# Power_5v.net
KiCad netlist of a schematic drawn in Altium Designer
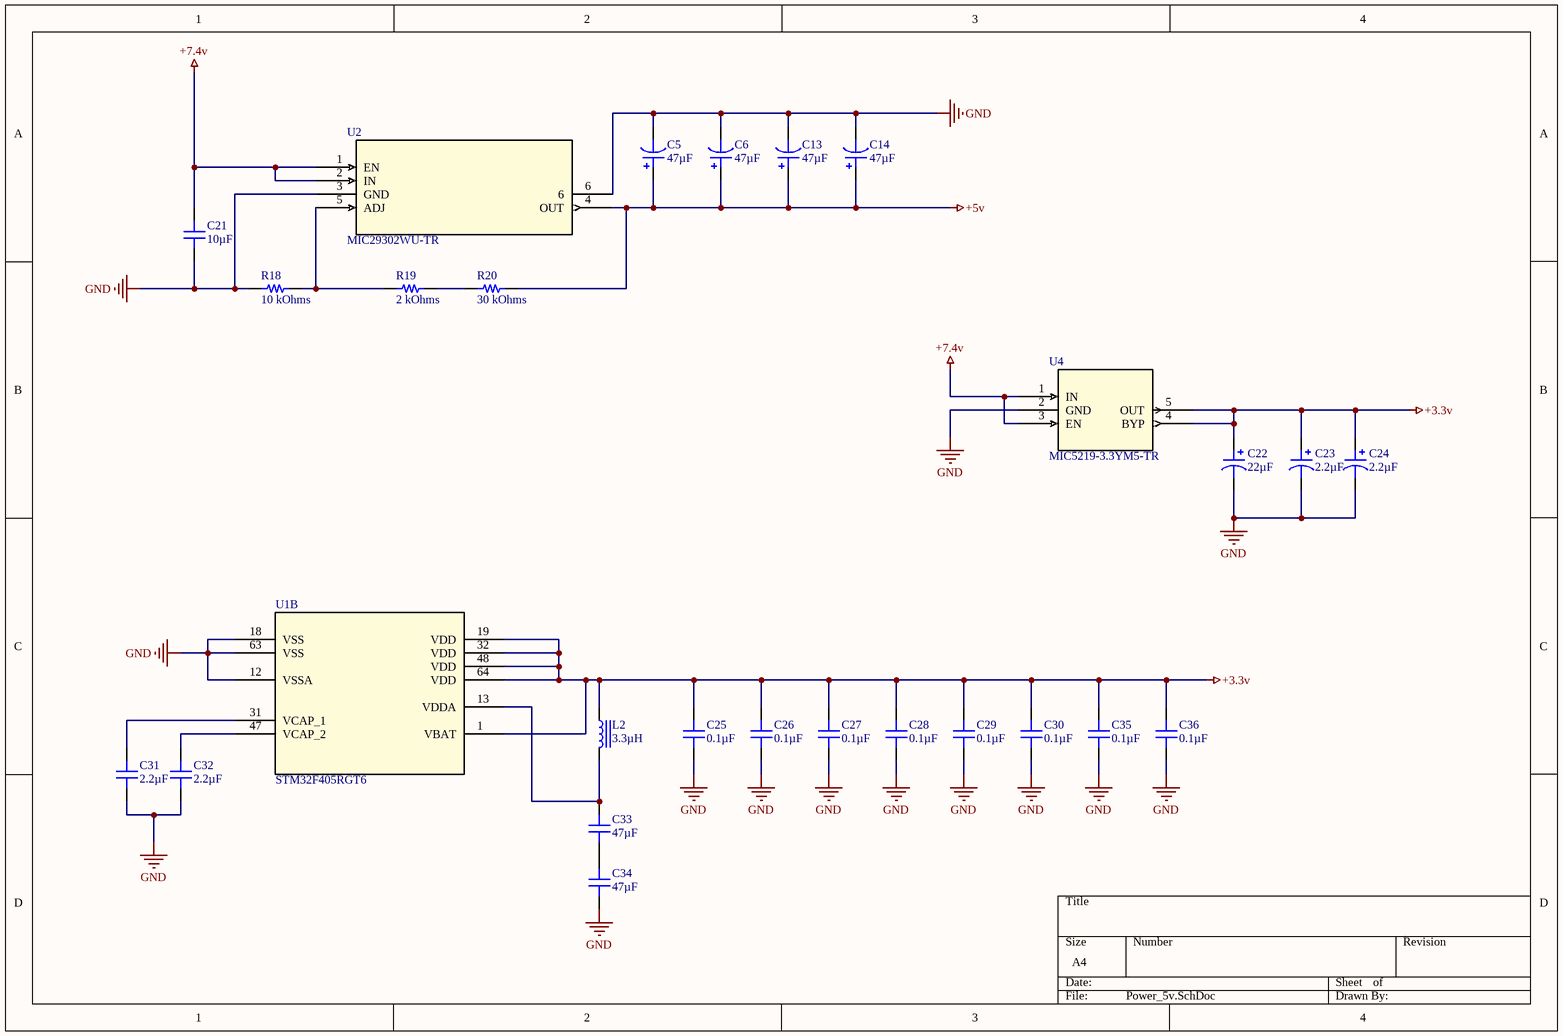
[diagram p0: Power_5v.SchDoc]

(export (version "E")
  (design (tool "Eeschema 10.0.6"))
  (components
    (comp (ref "C5")
      (value "47µF")
      (footprint "CAP POL 1411_3528")
      (description "CAP TANT 47UF 10% 10V 1411")
      (fields (field (name "PART NUMBER") "TPSB476K010R0250") (field (name "MANUFACTURER") "AVX Corporation"))
      (libsource (lib "Celestial Altium Library - altium_library") (part "Polarised Capacitor"))
    )
    (comp (ref "C6")
      (value "47µF")
      (footprint "CAP POL 1411_3528")
      (description "CAP TANT 47UF 10% 10V 1411")
      (fields (field (name "PART NUMBER") "TPSB476K010R0250") (field (name "MANUFACTURER") "AVX Corporation"))
      (libsource (lib "Celestial Altium Library - altium_library") (part "Polarised Capacitor"))
    )
    (comp (ref "C13")
      (value "47µF")
      (footprint "CAP POL 1411_3528")
      (description "CAP TANT 47UF 10% 10V 1411")
      (fields (field (name "PART NUMBER") "TPSB476K010R0250") (field (name "MANUFACTURER") "AVX Corporation"))
      (libsource (lib "Celestial Altium Library - altium_library") (part "Polarised Capacitor"))
    )
    (comp (ref "C14")
      (value "47µF")
      (footprint "CAP POL 1411_3528")
      (description "CAP TANT 47UF 10% 10V 1411")
      (fields (field (name "PART NUMBER") "TPSB476K010R0250") (field (name "MANUFACTURER") "AVX Corporation"))
      (libsource (lib "Celestial Altium Library - altium_library") (part "Polarised Capacitor"))
    )
    (comp (ref "C21")
      (value "10µF")
      (footprint "CAP 0805_2012")
      (description "CAP CER 10UF 25V JB 0805")
      (fields
        (field (name "PART NUMBER") "C2012JB1E106M125AB")
        (field (name "MANUFACTURER") "TDK Corporation")
      )
      (libsource (lib "Celestial Altium Library - altium_library") (part "Capacitor"))
    )
    (comp (ref "C22")
      (value "22µF")
      (footprint "CAP POL 1411_3528")
      (description "CAP TANT 22UF 10% 10V 1411")
      (fields (field (name "PART NUMBER") "T495B226K010ATE500") (field (name "MANUFACTURER") "KEMET"))
      (libsource (lib "Celestial Altium Library - altium_library") (part "Polarised Capacitor"))
    )
    (comp (ref "C23")
      (value "2.2µF")
      (footprint "CAP POL 1206_3216")
      (description "CAP TANT 2.2UF 10% 10V 1206")
      (fields (field (name "PART NUMBER") "T494A225K010AT") (field (name "MANUFACTURER") "KEMET"))
      (libsource (lib "Celestial Altium Library - altium_library") (part "Polarised Capacitor"))
    )
    (comp (ref "C24")
      (value "2.2µF")
      (footprint "CAP POL 1206_3216")
      (description "CAP TANT 2.2UF 10% 10V 1206")
      (fields (field (name "PART NUMBER") "T494A225K010AT") (field (name "MANUFACTURER") "KEMET"))
      (libsource (lib "Celestial Altium Library - altium_library") (part "Polarised Capacitor"))
    )
    (comp (ref "C25")
      (value "0.1µF")
      (footprint "CAP 0805_2012")
      (description "CAP CER 0.1UF 50V X7R 0805")
      (fields (field (name "PART NUMBER") "CC0805MRX7R9BB104") (field (name "MANUFACTURER") "Yageo"))
      (libsource (lib "Celestial Altium Library - altium_library") (part "Capacitor"))
    )
    (comp (ref "C26")
      (value "0.1µF")
      (footprint "CAP 0805_2012")
      (description "CAP CER 0.1UF 50V X7R 0805")
      (fields (field (name "PART NUMBER") "CC0805MRX7R9BB104") (field (name "MANUFACTURER") "Yageo"))
      (libsource (lib "Celestial Altium Library - altium_library") (part "Capacitor"))
    )
    (comp (ref "C27")
      (value "0.1µF")
      (footprint "CAP 0805_2012")
      (description "CAP CER 0.1UF 50V X7R 0805")
      (fields (field (name "PART NUMBER") "CC0805MRX7R9BB104") (field (name "MANUFACTURER") "Yageo"))
      (libsource (lib "Celestial Altium Library - altium_library") (part "Capacitor"))
    )
    (comp (ref "C28")
      (value "0.1µF")
      (footprint "CAP 0805_2012")
      (description "CAP CER 0.1UF 50V X7R 0805")
      (fields (field (name "PART NUMBER") "CC0805MRX7R9BB104") (field (name "MANUFACTURER") "Yageo"))
      (libsource (lib "Celestial Altium Library - altium_library") (part "Capacitor"))
    )
    (comp (ref "C29")
      (value "0.1µF")
      (footprint "CAP 0805_2012")
      (description "CAP CER 0.1UF 50V X7R 0805")
      (fields (field (name "PART NUMBER") "CC0805MRX7R9BB104") (field (name "MANUFACTURER") "Yageo"))
      (libsource (lib "Celestial Altium Library - altium_library") (part "Capacitor"))
    )
    (comp (ref "C30")
      (value "0.1µF")
      (footprint "CAP 0805_2012")
      (description "CAP CER 0.1UF 50V X7R 0805")
      (fields (field (name "PART NUMBER") "CC0805MRX7R9BB104") (field (name "MANUFACTURER") "Yageo"))
      (libsource (lib "Celestial Altium Library - altium_library") (part "Capacitor"))
    )
    (comp (ref "C31")
      (value "2.2µF")
      (footprint "CAP 0805_2012")
      (description "CAP CER 2.2UF 6.3V X7R 0805")
      (fields (field (name "PART NUMBER") "C0805C225K9RACTU") (field (name "MANUFACTURER") "KEMET"))
      (libsource (lib "Celestial Altium Library - altium_library") (part "Capacitor"))
    )
    (comp (ref "C32")
      (value "2.2µF")
      (footprint "CAP 0805_2012")
      (description "CAP CER 2.2UF 6.3V X7R 0805")
      (fields (field (name "PART NUMBER") "C0805C225K9RACTU") (field (name "MANUFACTURER") "KEMET"))
      (libsource (lib "Celestial Altium Library - altium_library") (part "Capacitor"))
    )
    (comp (ref "C33")
      (value "47µF")
      (footprint "CAP 0805_2012")
      (description "CAP CER 47UF 10V X5R 0805")
      (fields
        (field (name "PART NUMBER") "GRM21BR61A476ME15L")
        (field (name "MANUFACTURER") "Murata Electronics")
      )
      (libsource (lib "Celestial Altium Library - altium_library") (part "Capacitor"))
    )
    (comp (ref "C34")
      (value "47µF")
      (footprint "CAP 0805_2012")
      (description "CAP CER 47UF 10V X5R 0805")
      (fields
        (field (name "PART NUMBER") "GRM21BR61A476ME15L")
        (field (name "MANUFACTURER") "Murata Electronics")
      )
      (libsource (lib "Celestial Altium Library - altium_library") (part "Capacitor"))
    )
    (comp (ref "C35")
      (value "0.1µF")
      (footprint "CAP 0805_2012")
      (description "CAP CER 0.1UF 50V X7R 0805")
      (fields (field (name "PART NUMBER") "CC0805MRX7R9BB104") (field (name "MANUFACTURER") "Yageo"))
      (libsource (lib "Celestial Altium Library - altium_library") (part "Capacitor"))
    )
    (comp (ref "C36")
      (value "0.1µF")
      (footprint "CAP 0805_2012")
      (description "CAP CER 0.1UF 50V X7R 0805")
      (fields (field (name "PART NUMBER") "CC0805MRX7R9BB104") (field (name "MANUFACTURER") "Yageo"))
      (libsource (lib "Celestial Altium Library - altium_library") (part "Capacitor"))
    )
    (comp (ref "L2")
      (value "3.3µH")
      (footprint "IND 0806_2016")
      (description "FIXED IND 3.3UH 1.1A 130 MOHM")
      (fields (field (name "PART NUMBER") "74479776233") (field (name "MANUFACTURER") "Würth Elektronik"))
      (libsource (lib "Celestial Altium Library - altium_library") (part "Inductor"))
    )
    (comp (ref "R18")
      (value "10 kOhms")
      (footprint "RES 0805_2012")
      (description "CRGCQ 0805 10K 1%")
      (fields
        (field (name "PART NUMBER") "CRGCQ0805F10K")
        (field (name "MANUFACTURER") "TE Connectivity Passive Product")
      )
      (libsource (lib "Celestial Altium Library - altium_library") (part "Resistor"))
    )
    (comp (ref "R19")
      (value "2 kOhms")
      (footprint "RES 0805_2012")
      (description "RES 2K OHM 1% 1/8W 0805")
      (fields (field (name "PART NUMBER") "TNPW08052K00FEEA") (field (name "MANUFACTURER") "Vishay Dale"))
      (libsource (lib "Celestial Altium Library - altium_library") (part "Resistor"))
    )
    (comp (ref "R20")
      (value "30 kOhms")
      (footprint "RES 0805_2012")
      (description "RES 30K OHM 1% 1/8W 0805")
      (fields
        (field (name "PART NUMBER") "RMCF0805FT30K0")
        (field (name "MANUFACTURER") "Stackpole Electronics Inc")
      )
      (libsource (lib "Celestial Altium Library - altium_library") (part "Resistor"))
    )
    (comp (ref "U1")
      (value "STM32F405RGT6")
      (footprint "LQFP64-10x10mm")
      (description "No Description Available")
      (fields (field (name "COPYRIGHT") "Copyright (C) 2018 Accelerated Designs. All rights reserved"))
      (libsource (lib "STM32F405RGT6") (part "STM32F405RGT6"))
    )
    (comp (ref "U2")
      (value "MIC29302WU-TR")
      (footprint "TO-263-5_MCH")
      (description "No Description Available")
      (fields (field (name "COPYRIGHT") "Copyright (C) 2022 Ultra Librarian. All rights reserved."))
      (libsource (lib "MIC29302WU-TR") (part "MIC29302WU-TR"))
    )
    (comp (ref "U4")
      (value "MIC5219-3.3YM5-TR")
      (footprint "SOT-23-5_M5_MCH")
      (description "No Description Available")
      (fields (field (name "COPYRIGHT") "Copyright (C) 2018 Accelerated Designs. All rights reserved"))
      (libsource (lib "MIC521933YM5TR") (part "MIC5219-3.3YM5-TR"))
    )
  )
  (nets
    (net (code "1") (name "+3.3v") (class "Default")
      (node (ref "C22") (pin "1") (pinfunction "1_1") (pintype "passive"))
      (node (ref "C23") (pin "1") (pinfunction "1_1") (pintype "passive"))
      (node (ref "C24") (pin "1") (pinfunction "1_1") (pintype "passive"))
      (node (ref "C25") (pin "2") (pinfunction "2_2") (pintype "passive"))
      (node (ref "C26") (pin "2") (pinfunction "2_2") (pintype "passive"))
      (node (ref "C27") (pin "2") (pinfunction "2_2") (pintype "passive"))
      (node (ref "C28") (pin "2") (pinfunction "2_2") (pintype "passive"))
      (node (ref "C29") (pin "2") (pinfunction "2_2") (pintype "passive"))
      (node (ref "C30") (pin "2") (pinfunction "2_2") (pintype "passive"))
      (node (ref "C35") (pin "2") (pinfunction "2_2") (pintype "passive"))
      (node (ref "C36") (pin "2") (pinfunction "2_2") (pintype "passive"))
      (node (ref "L2") (pin "1") (pinfunction "1_1") (pintype "passive"))
      (node (ref "U1") (pin "1") (pinfunction "VBAT_1") (pintype "power_in"))
      (node (ref "U1") (pin "19") (pinfunction "VDD_19") (pintype "power_in"))
      (node (ref "U1") (pin "32") (pinfunction "VDD_32") (pintype "power_in"))
      (node (ref "U1") (pin "48") (pinfunction "VDD_48") (pintype "power_in"))
      (node (ref "U1") (pin "64") (pinfunction "VDD_64") (pintype "power_in"))
      (node (ref "U4") (pin "4") (pinfunction "BYP_4") (pintype "output"))
      (node (ref "U4") (pin "5") (pinfunction "OUT_5") (pintype "power_in"))
    )
    (net (code "2") (name "+5v") (class "Default")
      (node (ref "C13") (pin "1") (pinfunction "1_1") (pintype "passive"))
      (node (ref "C14") (pin "1") (pinfunction "1_1") (pintype "passive"))
      (node (ref "C5") (pin "1") (pinfunction "1_1") (pintype "passive"))
      (node (ref "C6") (pin "1") (pinfunction "1_1") (pintype "passive"))
      (node (ref "R20") (pin "2") (pinfunction "2_2") (pintype "passive"))
      (node (ref "U2") (pin "4") (pinfunction "OUT_4") (pintype "output"))
    )
    (net (code "3") (name "+7.4v") (class "Default")
      (node (ref "C21") (pin "2") (pinfunction "2_2") (pintype "passive"))
      (node (ref "U2") (pin "1") (pinfunction "EN_1") (pintype "input"))
      (node (ref "U2") (pin "2") (pinfunction "IN_2") (pintype "input"))
      (node (ref "U4") (pin "1") (pinfunction "IN_1") (pintype "input"))
      (node (ref "U4") (pin "3") (pinfunction "EN_3") (pintype "input"))
    )
    (net (code "4") (name "GND") (class "Default")
      (node (ref "C13") (pin "2") (pinfunction "2_2") (pintype "passive"))
      (node (ref "C14") (pin "2") (pinfunction "2_2") (pintype "passive"))
      (node (ref "C21") (pin "1") (pinfunction "1_1") (pintype "passive"))
      (node (ref "C22") (pin "2") (pinfunction "2_2") (pintype "passive"))
      (node (ref "C23") (pin "2") (pinfunction "2_2") (pintype "passive"))
      (node (ref "C24") (pin "2") (pinfunction "2_2") (pintype "passive"))
      (node (ref "C25") (pin "1") (pinfunction "1_1") (pintype "passive"))
      (node (ref "C26") (pin "1") (pinfunction "1_1") (pintype "passive"))
      (node (ref "C27") (pin "1") (pinfunction "1_1") (pintype "passive"))
      (node (ref "C28") (pin "1") (pinfunction "1_1") (pintype "passive"))
      (node (ref "C29") (pin "1") (pinfunction "1_1") (pintype "passive"))
      (node (ref "C30") (pin "1") (pinfunction "1_1") (pintype "passive"))
      (node (ref "C31") (pin "1") (pinfunction "1_1") (pintype "passive"))
      (node (ref "C32") (pin "1") (pinfunction "1_1") (pintype "passive"))
      (node (ref "C34") (pin "1") (pinfunction "1_1") (pintype "passive"))
      (node (ref "C35") (pin "1") (pinfunction "1_1") (pintype "passive"))
      (node (ref "C36") (pin "1") (pinfunction "1_1") (pintype "passive"))
      (node (ref "C5") (pin "2") (pinfunction "2_2") (pintype "passive"))
      (node (ref "C6") (pin "2") (pinfunction "2_2") (pintype "passive"))
      (node (ref "R18") (pin "1") (pinfunction "1_1") (pintype "passive"))
      (node (ref "U1") (pin "12") (pinfunction "VSSA_12") (pintype "power_in"))
      (node (ref "U1") (pin "18") (pinfunction "VSS_18") (pintype "power_in"))
      (node (ref "U1") (pin "63") (pinfunction "VSS_63") (pintype "power_in"))
      (node (ref "U2") (pin "3") (pinfunction "GND_3") (pintype "power_in"))
      (node (ref "U2") (pin "6") (pinfunction "6_6") (pintype "passive"))
      (node (ref "U4") (pin "2") (pinfunction "GND_2") (pintype "power_in"))
    )
    (net (code "5") (name "Net-(C33-Pad1)") (class "Default")
      (node (ref "C33") (pin "1") (pinfunction "1_1") (pintype "passive"))
      (node (ref "C34") (pin "2") (pinfunction "2_2") (pintype "passive"))
    )
    (net (code "6") (name "Net-(R19-Pad2)") (class "Default")
      (node (ref "R19") (pin "2") (pinfunction "2_2") (pintype "passive"))
      (node (ref "R20") (pin "1") (pinfunction "1_1") (pintype "passive"))
    )
    (net (code "7") (name "Net-(U1B-VCAP_1)") (class "Default")
      (node (ref "C31") (pin "2") (pinfunction "2_2") (pintype "passive"))
      (node (ref "U1") (pin "31") (pinfunction "VCAP_1_31") (pintype "power_in"))
    )
    (net (code "8") (name "Net-(U1B-VCAP_2)") (class "Default")
      (node (ref "C32") (pin "2") (pinfunction "2_2") (pintype "passive"))
      (node (ref "U1") (pin "47") (pinfunction "VCAP_2_47") (pintype "power_in"))
    )
    (net (code "9") (name "Net-(U1B-VDDA)") (class "Default")
      (node (ref "C33") (pin "2") (pinfunction "2_2") (pintype "passive"))
      (node (ref "L2") (pin "2") (pinfunction "2_2") (pintype "passive"))
      (node (ref "U1") (pin "13") (pinfunction "VDDA_13") (pintype "power_in"))
    )
    (net (code "10") (name "Net-(U2-ADJ)") (class "Default")
      (node (ref "R18") (pin "2") (pinfunction "2_2") (pintype "passive"))
      (node (ref "R19") (pin "1") (pinfunction "1_1") (pintype "passive"))
      (node (ref "U2") (pin "5") (pinfunction "ADJ_5") (pintype "input"))
    )
  )
)
